# ThermistorSim.net
KiCad netlist of a schematic drawn in Altium Designer
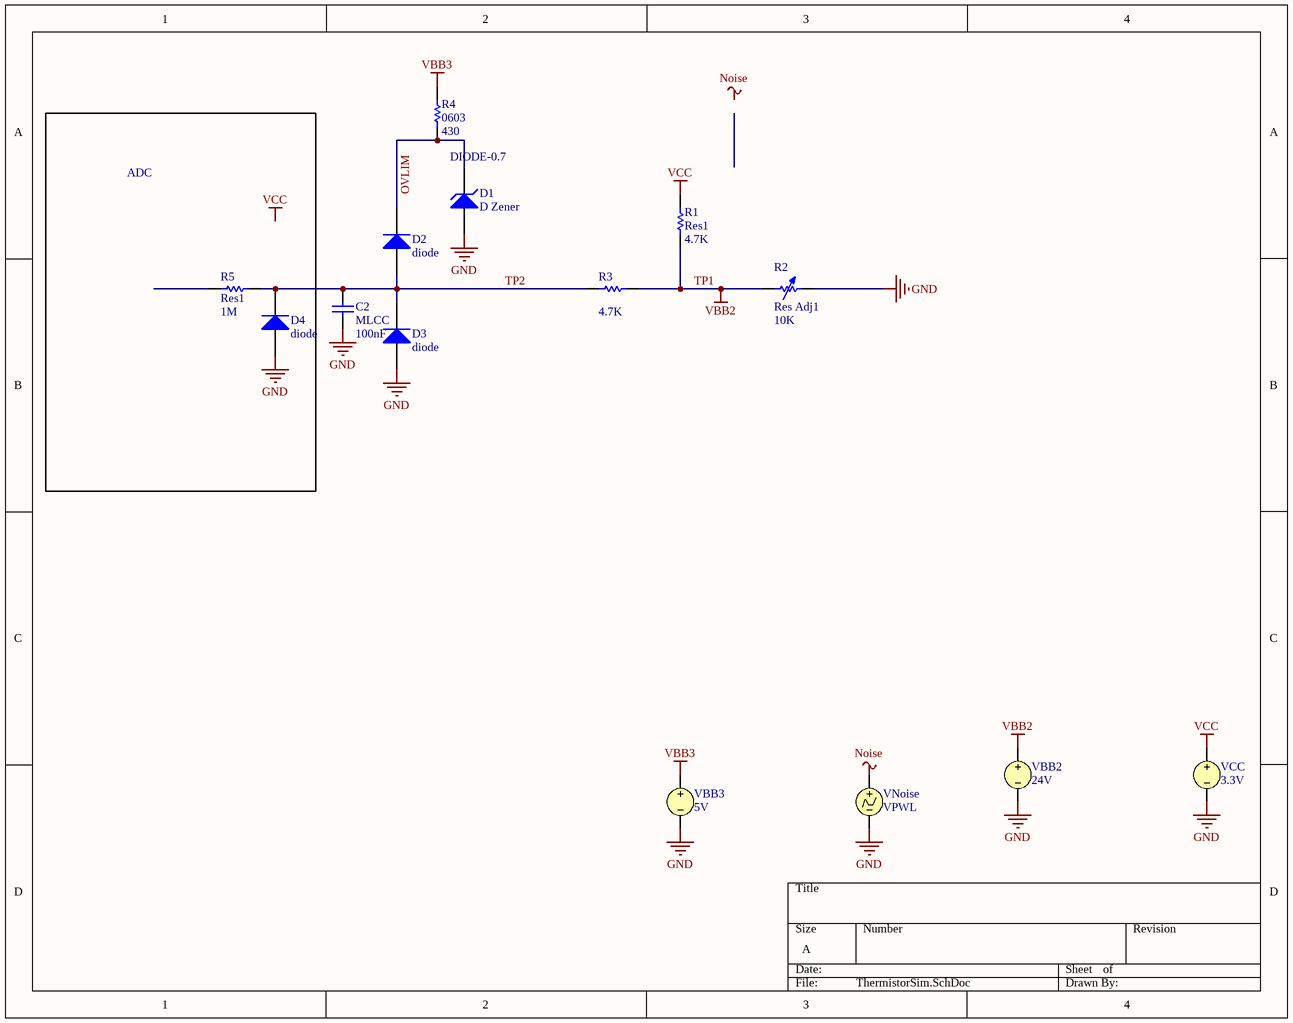
[diagram p0: ThermistorSim.SchDoc]

(export (version "E")
  (design (tool "Eeschema 10.0.6"))
  (components
    (comp (ref "C2")
      (value "MLCC")
      (footprint "RAD-0.3")
      (description "Capacitor")
      (fields (field (name "ALTIUM_VALUE") "100nF") (field (name "PUBLISHER") "Altium Limited"))
      (libsource (lib "Miscellaneous Devices") (part "Cap"))
    )
    (comp (ref "D1")
      (value "D Zener")
      (footprint "DIODE-0.7")
      (description "Zener Diode")
      (fields (field (name "PACKAGEREFERENCE") "DIODE-0.7") (field (name "PUBLISHER") "Altium Limited"))
      (libsource (lib "Miscellaneous Devices") (part "D Zener"))
    )
    (comp (ref "D2")
      (value "diode")
      (footprint "SMC")
      (description "Default Diode")
      (fields (field (name "PUBLISHER") "Altium Limited"))
      (libsource (lib "Miscellaneous Devices") (part "Diode"))
    )
    (comp (ref "D3")
      (value "diode")
      (footprint "SMC")
      (description "Default Diode")
      (fields (field (name "PUBLISHER") "Altium Limited"))
      (libsource (lib "Miscellaneous Devices") (part "Diode"))
    )
    (comp (ref "D4")
      (value "diode")
      (footprint "SMC")
      (description "Default Diode")
      (fields (field (name "PUBLISHER") "Altium Limited"))
      (libsource (lib "Miscellaneous Devices") (part "Diode"))
    )
    (comp (ref "R1")
      (value "Res1")
      (footprint "AXIAL-0.3")
      (description "Resistor")
      (fields (field (name "ALTIUM_VALUE") "4.7K") (field (name "PUBLISHER") "Altium Limited"))
      (libsource (lib "Miscellaneous Devices") (part "Res1"))
    )
    (comp (ref "R2")
      (value "Res Adj1")
      (footprint "AXIAL-0.7")
      (description "Variable Resistor")
      (fields (field (name "ALTIUM_VALUE") "10K") (field (name "PUBLISHER") "Altium Limited"))
      (libsource (lib "Miscellaneous Devices") (part "Res Adj1"))
    )
    (comp (ref "R3")
      (value "4.7K")
      (footprint "AXIAL-0.3")
      (description "Resistor")
      (fields (field (name "PUBLISHER") "Altium Limited"))
      (libsource (lib "Miscellaneous Devices") (part "Res1"))
    )
    (comp (ref "R4")
      (value "0603")
      (footprint "AXIAL-0.3")
      (description "Resistor")
      (fields (field (name "ALTIUM_VALUE") "430") (field (name "PUBLISHER") "Altium Limited"))
      (libsource (lib "Miscellaneous Devices") (part "Res1"))
    )
    (comp (ref "R5")
      (value "Res1")
      (footprint "AXIAL-0.3")
      (description "Resistor")
      (fields (field (name "ALTIUM_VALUE") "1M") (field (name "PUBLISHER") "Altium Limited"))
      (libsource (lib "Miscellaneous Devices") (part "Res1"))
    )
    (comp (ref "VBB2")
      (value "24V")
      (description "Voltage Source")
      (fields (field (name "PUBLISHER") "Altium Limited"))
      (libsource (lib "Simulation Sources") (part "VSRC"))
    )
    (comp (ref "VBB3")
      (value "5V")
      (description "Voltage Source")
      (fields (field (name "PUBLISHER") "Altium Limited"))
      (libsource (lib "Simulation Sources") (part "VSRC"))
    )
    (comp (ref "VCC")
      (value "3.3V")
      (description "Voltage Source")
      (fields (field (name "PUBLISHER") "Altium Limited"))
      (libsource (lib "Simulation Sources") (part "VSRC"))
    )
    (comp (ref "VNoise")
      (value "VPWL")
      (description "Piecewise Linear Voltage Source")
      (fields (field (name "PUBLISHER") "Altium Limited"))
      (libsource (lib "Simulation Sources") (part "VPWL"))
    )
  )
  (nets
    (net (code "1") (name "/OVLIM") (class "Default")
      (node (ref "D1") (pin "2") (pinfunction "K_2") (pintype "passive"))
      (node (ref "D2") (pin "2") (pinfunction "K_2") (pintype "passive"))
      (node (ref "R4") (pin "1") (pinfunction "1_1") (pintype "passive"))
    )
    (net (code "2") (name "/TP2") (class "Default")
      (node (ref "C2") (pin "2") (pinfunction "2_2") (pintype "passive"))
      (node (ref "D2") (pin "1") (pinfunction "A_1") (pintype "passive"))
      (node (ref "D3") (pin "2") (pinfunction "K_2") (pintype "passive"))
      (node (ref "D4") (pin "2") (pinfunction "K_2") (pintype "passive"))
      (node (ref "R3") (pin "1") (pinfunction "1_1") (pintype "passive"))
      (node (ref "R5") (pin "1") (pinfunction "1_1") (pintype "passive"))
    )
    (net (code "3") (name "GND") (class "Default")
      (node (ref "C2") (pin "1") (pinfunction "1_1") (pintype "passive"))
      (node (ref "D1") (pin "1") (pinfunction "A_1") (pintype "passive"))
      (node (ref "D3") (pin "1") (pinfunction "A_1") (pintype "passive"))
      (node (ref "D4") (pin "1") (pinfunction "A_1") (pintype "passive"))
      (node (ref "R2") (pin "2") (pinfunction "2_2") (pintype "passive"))
      (node (ref "VBB2") (pin "2") (pinfunction "2_2") (pintype "passive"))
      (node (ref "VBB3") (pin "2") (pinfunction "2_2") (pintype "passive"))
      (node (ref "VCC") (pin "2") (pinfunction "2_2") (pintype "passive"))
      (node (ref "VNoise") (pin "2") (pinfunction "2_2") (pintype "passive"))
    )
    (net (code "4") (name "Noise") (class "Default")
      (node (ref "VNoise") (pin "1") (pinfunction "1_1") (pintype "passive"))
    )
    (net (code "5") (name "VBB2") (class "Default")
      (node (ref "R1") (pin "1") (pinfunction "1_1") (pintype "passive"))
      (node (ref "R2") (pin "1") (pinfunction "1_1") (pintype "passive"))
      (node (ref "R3") (pin "2") (pinfunction "2_2") (pintype "passive"))
      (node (ref "VBB2") (pin "1") (pinfunction "1_1") (pintype "passive"))
    )
    (net (code "6") (name "VBB3") (class "Default")
      (node (ref "R4") (pin "2") (pinfunction "2_2") (pintype "passive"))
      (node (ref "VBB3") (pin "1") (pinfunction "1_1") (pintype "passive"))
    )
    (net (code "7") (name "VCC") (class "Default")
      (node (ref "R1") (pin "2") (pinfunction "2_2") (pintype "passive"))
      (node (ref "VCC") (pin "1") (pinfunction "1_1") (pintype "passive"))
    )
    (net (code "8") (name "unconnected-(R5-Pad2)") (class "Default")
      (node (ref "R5") (pin "2") (pinfunction "2_2") (pintype "passive"))
    )
  )
)
